# led_frontend.net
KiCad netlist of a schematic drawn in Altium Designer
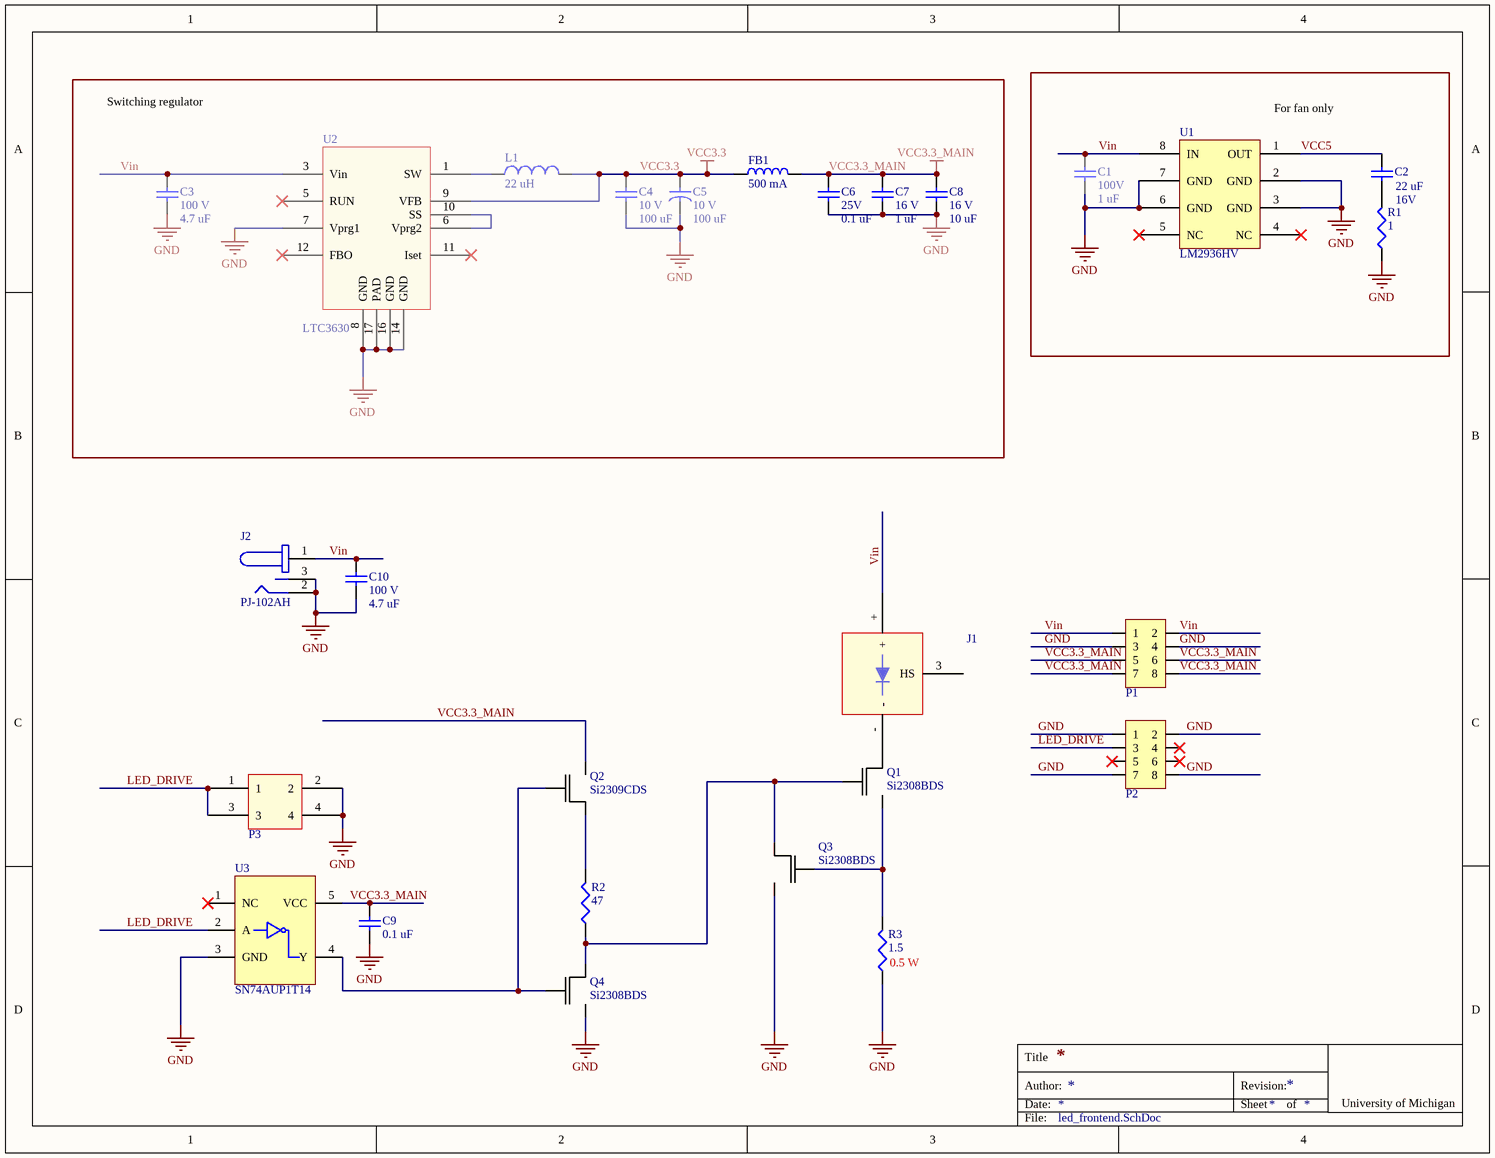
[diagram p0: led_frontend.SchDoc]

(export (version "E")
  (design (tool "Eeschema 10.0.6"))
  (components
    (comp (ref "C1")
      (value "1 uF")
      (footprint "0805")
      (description "Ceramic capacitor, 1 uF, 100 V, 0805 package")
      (fields
        (field (name "TOLERANCE") "10%")
        (field (name "VOLTAGE RATED") "100V")
        (field (name "Comment") "Ceramic capacitor")
      )
      (libsource (lib "rlc") (part "C_1u_100V_0805_ceramic"))
    )
    (comp (ref "C2")
      (value "22 uF")
      (footprint "1206")
      (description "Ceramic capacitor, 22 uF, 1206 package")
      (fields
        (field (name "VOLTAGE RATED") "16V")
        (field (name "TOLERANCE") "20%")
        (field (name "Comment") "Ceramic capacitor")
      )
      (libsource (lib "rlc") (part "C_22u_16V_1206_ceramic"))
    )
    (comp (ref "C3")
      (value "4.7 uF")
      (footprint "2220")
      (description "Ceramic capacitor, 4.7u, 2220 package")
      (fields
        (field (name "TOLERANCE") "20%")
        (field (name "VOLTAGE RATED") "100 V")
        (field (name "Comment") "Ceramic capacitor")
      )
      (libsource (lib "rlc") (part "C_4.7u_2220_ceramic"))
    )
    (comp (ref "C4")
      (value "100 uF")
      (footprint "1210")
      (description "Ceramic capacitor, 100u, 1210 package")
      (fields
        (field (name "TOLERANCE") "20%")
        (field (name "VOLTAGE RATED") "10 V")
        (field (name "Comment") "Ceramic capacitor")
      )
      (libsource (lib "rlc") (part "C_100u_1210_ceramic"))
    )
    (comp (ref "C5")
      (value "100 uF")
      (footprint "2917")
      (description "Tantalum capacitor, 100u, 2917 package")
      (fields
        (field (name "TOLERANCE") "10%")
        (field (name "VOLTAGE RATED") "10 V")
        (field (name "Comment") "Ceramic capacitor")
      )
      (libsource (lib "rlc") (part "C_100u_2917_tantalum"))
    )
    (comp (ref "C6")
      (value "0.1 uF")
      (footprint "0603")
      (description "Ceramic capacitor, 0.1 uF, 0603 package")
      (fields
        (field (name "VOLTAGE RATED") "25V")
        (field (name "TOLERANCE") "10%")
        (field (name "Comment") "Ceramic capacitor")
      )
      (libsource (lib "rlc") (part "C_0.1u_25V_0603_ceramic"))
    )
    (comp (ref "C7")
      (value "1 uF")
      (footprint "0603")
      (description "Ceramic capacitor, 1 uF, 16 V, 0603 package")
      (fields
        (field (name "TOLERANCE") "10%")
        (field (name "VOLTAGE RATED") "16 V")
        (field (name "Comment") "Ceramic capacitor")
      )
      (libsource (lib "rlc") (part "C_1u_16V_0603_ceramic"))
    )
    (comp (ref "C8")
      (value "10 uF")
      (footprint "0603")
      (description "Ceramic capacitor, 10 uF, 16 V, 0603 package")
      (fields
        (field (name "TOLERANCE") "20%")
        (field (name "VOLTAGE RATED") "16 V")
        (field (name "Comment") "Ceramic capacitor")
      )
      (libsource (lib "rlc") (part "C_10u_16V_0603_ceramic"))
    )
    (comp (ref "C9")
      (value "0.1 uF")
      (footprint "0603")
      (description "Ceramic capacitor, 0.1 uF, 0603 package")
      (fields (field (name "TOLERANCE") "10%") (field (name "Comment") "Ceramic capacitor"))
      (libsource (lib "rlc") (part "C_0.1u_25V_0603_ceramic"))
    )
    (comp (ref "C10")
      (value "4.7 uF")
      (footprint "2220")
      (description "Ceramic capacitor, 4.7u, 2220 package")
      (fields
        (field (name "TOLERANCE") "20%")
        (field (name "VOLTAGE RATED") "100 V")
        (field (name "Comment") "Ceramic capacitor")
      )
      (libsource (lib "rlc") (part "C_4.7u_2220_ceramic"))
    )
    (comp (ref "FB1")
      (value "Ferrite Bead")
      (footprint "0603")
      (description "Ferrite Bead, 500 mA, 0603 package")
      (fields (field (name "CURRENT RATING") "500 mA"))
      (libsource (lib "rlc") (part "FB_500mA_0603"))
    )
    (comp (ref "J1")
      (value "1807200002")
      (footprint "molex")
      (description "LED Array Holders  for CREE* XLamp†   Arrays")
      (libsource (lib "connectors") (part "Molex LED holder"))
    )
    (comp (ref "J2")
      (value "PJ-102AH")
      (footprint "PJ-102AH")
      (description "CONN PWR JACK 2.1X5.5MM HIGH CUR")
      (libsource (lib "connectors") (part "PJ-102AH"))
    )
    (comp (ref "L1")
      (value "22 uH")
      (footprint "SLF10145")
      (description "Inductor, 22 uH, TDK SLF10145")
      (fields (field (name "Comment") "L_22uH_SLF10145"))
      (libsource (lib "rlc") (part "L_22uH_SLF10145"))
    )
    (comp (ref "P1")
      (value "HW-04-20-F-D-900-SM")
      (footprint "HW-04-20-F-D-900-SM")
      (description "Samtec 2x4 100 mil connector")
      (libsource (lib "connectors") (part "HW-04-20-F-D-900-SM"))
    )
    (comp (ref "P2")
      (value "HW-04-20-F-D-900-SM")
      (footprint "HW-04-20-F-D-900-SM")
      (description "Samtec 2x4 100 mil connector")
      (libsource (lib "connectors") (part "HW-04-20-F-D-900-SM"))
    )
    (comp (ref "P3")
      (value "2 x 2 header SMD")
      (footprint "2x2 header SMD")
      (description "2x2 100 mil header SMD")
      (libsource (lib "connectors") (part "2 x 2 header SMD"))
    )
    (comp (ref "Q1")
      (value "Si2308BDS")
      (footprint "SOT23-3")
      (description "N-Channel 60-V (D-S) MOSFET")
      (libsource (lib "transistors") (part "Si2308BDS"))
    )
    (comp (ref "Q2")
      (value "Si2309CDS")
      (footprint "SOT23-3")
      (description "P-Channel 60-V (D-S) MOSFET")
      (libsource (lib "transistors") (part "Si2309CDS"))
    )
    (comp (ref "Q3")
      (value "Si2308BDS")
      (footprint "SOT23-3")
      (description "N-Channel 60-V (D-S) MOSFET")
      (libsource (lib "transistors") (part "Si2308BDS"))
    )
    (comp (ref "Q4")
      (value "Si2308BDS")
      (footprint "SOT23-3")
      (description "N-Channel 60-V (D-S) MOSFET")
      (libsource (lib "transistors") (part "Si2308BDS"))
    )
    (comp (ref "R1")
      (value "1")
      (footprint "0603")
      (description "Chip resistor, 1,  0603 package")
      (fields (field (name "TOLERANCE") "1%") (field (name "POWER") "1/10 W"))
      (libsource (lib "rlc") (part "R_1_0603"))
    )
    (comp (ref "R2")
      (value "47")
      (footprint "0603")
      (description "Chip resistor, 47, 0603 package")
      (fields (field (name "TOLERANCE") "1%") (field (name "POWER") "1/10 W"))
      (libsource (lib "rlc") (part "R_47_0603"))
    )
    (comp (ref "R3")
      (value "1.5")
      (footprint "1210")
      (description "Chip resistor, 1.5, 1210 package")
      (fields (field (name "POWER") "0.5 W") (field (name "Comment") "Chip resistor"))
      (libsource (lib "rlc") (part "R_1.5_1210"))
    )
    (comp (ref "U1")
      (value "LM2936HV")
      (footprint "SOIC-8")
      (description "Ultra-Low Quiescent Current LDO Voltage Regulator")
      (libsource (lib "voltage_regulators") (part "LM2936HV"))
    )
    (comp (ref "U2")
      (value "LTC3630")
      (footprint "MSE16(12)")
      (description "High Efficiency, 65V 500mA synchronous Step-Down Converter")
      (libsource (lib "voltage_regulators") (part "LTC3630"))
    )
    (comp (ref "U3")
      (value "SN74AUP1T14")
      (footprint "SC-70-5 (DCK)")
      (description "LOW POWER, 1.8/2.5/3.3-V INPUT, 3.3-V CMOS OUTPUT, SINGLE  SCHMITT-TRIGGER INVERTER GATE")
      (libsource (lib "logics") (part "SN74AUP1T14"))
    )
  )
  (nets
    (net (code "1") (name "/LED_DRIVE") (class "Default")
      (node (ref "P2") (pin "3") (pinfunction "3_3") (pintype "passive"))
      (node (ref "P3") (pin "1") (pinfunction "1_1") (pintype "passive"))
      (node (ref "P3") (pin "3") (pinfunction "3_3") (pintype "passive"))
      (node (ref "U3") (pin "2") (pinfunction "A_2") (pintype "power_in"))
    )
    (net (code "2") (name "/VCC5") (class "Default")
      (node (ref "C2") (pin "1") (pintype "passive"))
      (node (ref "U1") (pin "1") (pinfunction "OUT_1") (pintype "passive"))
    )
    (net (code "3") (name "/Vin") (class "Default")
      (node (ref "C1") (pin "1") (pintype "passive"))
      (node (ref "C10") (pin "1") (pintype "passive"))
      (node (ref "C3") (pin "1") (pintype "passive"))
      (node (ref "J1") (pin "+") (pinfunction "+_+") (pintype "passive"))
      (node (ref "J2") (pin "1") (pintype "passive"))
      (node (ref "P1") (pin "1") (pinfunction "1_1") (pintype "passive"))
      (node (ref "P1") (pin "2") (pinfunction "2_2") (pintype "passive"))
      (node (ref "U1") (pin "8") (pinfunction "IN_8") (pintype "passive"))
      (node (ref "U2") (pin "3") (pinfunction "Vin_3") (pintype "passive"))
    )
    (net (code "4") (name "GND") (class "Default")
      (node (ref "C1") (pin "2") (pintype "passive"))
      (node (ref "C10") (pin "2") (pintype "passive"))
      (node (ref "C3") (pin "2") (pintype "passive"))
      (node (ref "C4") (pin "2") (pintype "passive"))
      (node (ref "C5") (pin "2") (pintype "passive"))
      (node (ref "C6") (pin "2") (pintype "passive"))
      (node (ref "C7") (pin "2") (pintype "passive"))
      (node (ref "C8") (pin "2") (pintype "passive"))
      (node (ref "C9") (pin "2") (pintype "passive"))
      (node (ref "J2") (pin "2") (pintype "passive"))
      (node (ref "J2") (pin "3") (pintype "passive"))
      (node (ref "P1") (pin "3") (pinfunction "3_3") (pintype "passive"))
      (node (ref "P1") (pin "4") (pinfunction "4_4") (pintype "power_in"))
      (node (ref "P2") (pin "1") (pinfunction "1_1") (pintype "passive"))
      (node (ref "P2") (pin "2") (pinfunction "2_2") (pintype "passive"))
      (node (ref "P2") (pin "7") (pinfunction "7_7") (pintype "power_in"))
      (node (ref "P2") (pin "8") (pinfunction "8_8") (pintype "power_in"))
      (node (ref "P3") (pin "2") (pinfunction "2_2") (pintype "passive"))
      (node (ref "P3") (pin "4") (pinfunction "4_4") (pintype "passive"))
      (node (ref "Q3") (pin "2") (pinfunction "S_2") (pintype "passive"))
      (node (ref "Q4") (pin "2") (pinfunction "S_2") (pintype "passive"))
      (node (ref "R1") (pin "2") (pintype "passive"))
      (node (ref "R3") (pin "2") (pintype "passive"))
      (node (ref "U1") (pin "2") (pinfunction "GND_2") (pintype "passive"))
      (node (ref "U1") (pin "3") (pinfunction "GND_3") (pintype "passive"))
      (node (ref "U1") (pin "6") (pinfunction "GND_6") (pintype "passive"))
      (node (ref "U1") (pin "7") (pinfunction "GND_7") (pintype "passive"))
      (node (ref "U2") (pin "14") (pinfunction "GND_14") (pintype "passive"))
      (node (ref "U2") (pin "16") (pinfunction "GND_16") (pintype "passive"))
      (node (ref "U2") (pin "17") (pinfunction "PAD_17") (pintype "passive"))
      (node (ref "U2") (pin "7") (pinfunction "Vprg1_7") (pintype "passive"))
      (node (ref "U2") (pin "8") (pinfunction "GND_8") (pintype "passive"))
      (node (ref "U3") (pin "3") (pinfunction "GND_3") (pintype "power_in"))
    )
    (net (code "5") (name "Net-(C2-Pad2)") (class "Default")
      (node (ref "C2") (pin "2") (pintype "passive"))
      (node (ref "R1") (pin "1") (pintype "passive"))
    )
    (net (code "6") (name "Net-(Q1-D)") (class "Default")
      (node (ref "J1") (pin "-") (pinfunction "-_-") (pintype "passive"))
      (node (ref "Q1") (pin "3") (pinfunction "D_3") (pintype "passive"))
    )
    (net (code "7") (name "Net-(Q1-G)") (class "Default")
      (node (ref "Q1") (pin "1") (pinfunction "G_1") (pintype "passive"))
      (node (ref "Q3") (pin "3") (pinfunction "D_3") (pintype "passive"))
      (node (ref "Q4") (pin "3") (pinfunction "D_3") (pintype "passive"))
      (node (ref "R2") (pin "2") (pintype "passive"))
    )
    (net (code "8") (name "Net-(Q1-S)") (class "Default")
      (node (ref "Q1") (pin "2") (pinfunction "S_2") (pintype "passive"))
      (node (ref "Q3") (pin "1") (pinfunction "G_1") (pintype "passive"))
      (node (ref "R3") (pin "1") (pintype "passive"))
    )
    (net (code "9") (name "Net-(Q2-D)") (class "Default")
      (node (ref "Q2") (pin "3") (pinfunction "D_3") (pintype "passive"))
      (node (ref "R2") (pin "1") (pintype "passive"))
    )
    (net (code "10") (name "Net-(Q2-G)") (class "Default")
      (node (ref "Q2") (pin "1") (pinfunction "G_1") (pintype "passive"))
      (node (ref "Q4") (pin "1") (pinfunction "G_1") (pintype "passive"))
      (node (ref "U3") (pin "4") (pinfunction "Y_4") (pintype "power_in"))
    )
    (net (code "11") (name "Net-(U2-SS)") (class "Default")
      (node (ref "U2") (pin "10") (pinfunction "SS_10") (pintype "passive"))
      (node (ref "U2") (pin "6") (pinfunction "Vprg2_6") (pintype "passive"))
    )
    (net (code "12") (name "Net-(U2-SW)") (class "Default")
      (node (ref "L1") (pin "2") (pinfunction "2_2") (pintype "passive"))
      (node (ref "U2") (pin "1") (pinfunction "SW_1") (pintype "passive"))
    )
    (net (code "13") (name "VCC3.3") (class "Default")
      (node (ref "C4") (pin "1") (pintype "passive"))
      (node (ref "C5") (pin "1") (pintype "passive"))
      (node (ref "FB1") (pin "2") (pintype "passive"))
      (node (ref "L1") (pin "1") (pinfunction "1_1") (pintype "passive"))
      (node (ref "U2") (pin "9") (pinfunction "VFB_9") (pintype "passive"))
    )
    (net (code "14") (name "VCC3.3_MAIN") (class "Default")
      (node (ref "C6") (pin "1") (pintype "passive"))
      (node (ref "C7") (pin "1") (pintype "passive"))
      (node (ref "C8") (pin "1") (pintype "passive"))
      (node (ref "C9") (pin "1") (pintype "passive"))
      (node (ref "FB1") (pin "1") (pintype "passive"))
      (node (ref "P1") (pin "5") (pinfunction "5_5") (pintype "power_in"))
      (node (ref "P1") (pin "6") (pinfunction "6_6") (pintype "power_in"))
      (node (ref "P1") (pin "7") (pinfunction "7_7") (pintype "power_in"))
      (node (ref "P1") (pin "8") (pinfunction "8_8") (pintype "power_in"))
      (node (ref "Q2") (pin "2") (pinfunction "S_2") (pintype "passive"))
      (node (ref "U3") (pin "5") (pinfunction "VCC_5") (pintype "power_in"))
    )
    (net (code "15") (name "unconnected-(J1-HS-Pad3)") (class "Default")
      (node (ref "J1") (pin "3") (pinfunction "HS_3") (pintype "passive"))
    )
    (net (code "16") (name "unconnected-(P2-Pad4)") (class "Default")
      (node (ref "P2") (pin "4") (pinfunction "4_4") (pintype "power_in+no_connect"))
    )
    (net (code "17") (name "unconnected-(P2-Pad5)") (class "Default")
      (node (ref "P2") (pin "5") (pinfunction "5_5") (pintype "power_in+no_connect"))
    )
    (net (code "18") (name "unconnected-(P2-Pad6)") (class "Default")
      (node (ref "P2") (pin "6") (pinfunction "6_6") (pintype "power_in+no_connect"))
    )
    (net (code "19") (name "unconnected-(U1-NC-Pad4)") (class "Default")
      (node (ref "U1") (pin "4") (pinfunction "NC_4") (pintype "passive+no_connect"))
    )
    (net (code "20") (name "unconnected-(U1-NC-Pad5)") (class "Default")
      (node (ref "U1") (pin "5") (pinfunction "NC_5") (pintype "passive+no_connect"))
    )
    (net (code "21") (name "unconnected-(U2-FBO-Pad12)") (class "Default")
      (node (ref "U2") (pin "12") (pinfunction "FBO_12") (pintype "passive+no_connect"))
    )
    (net (code "22") (name "unconnected-(U2-Iset-Pad11)") (class "Default")
      (node (ref "U2") (pin "11") (pinfunction "Iset_11") (pintype "passive+no_connect"))
    )
    (net (code "23") (name "unconnected-(U2-RUN-Pad5)") (class "Default")
      (node (ref "U2") (pin "5") (pinfunction "RUN_5") (pintype "passive+no_connect"))
    )
    (net (code "24") (name "unconnected-(U3-NC-Pad1)") (class "Default")
      (node (ref "U3") (pin "1") (pinfunction "NC_1") (pintype "power_in+no_connect"))
    )
  )
)
